# Arduino-DUE-SHEILD-4X4.net
KiCad netlist of a schematic drawn in EAGLE
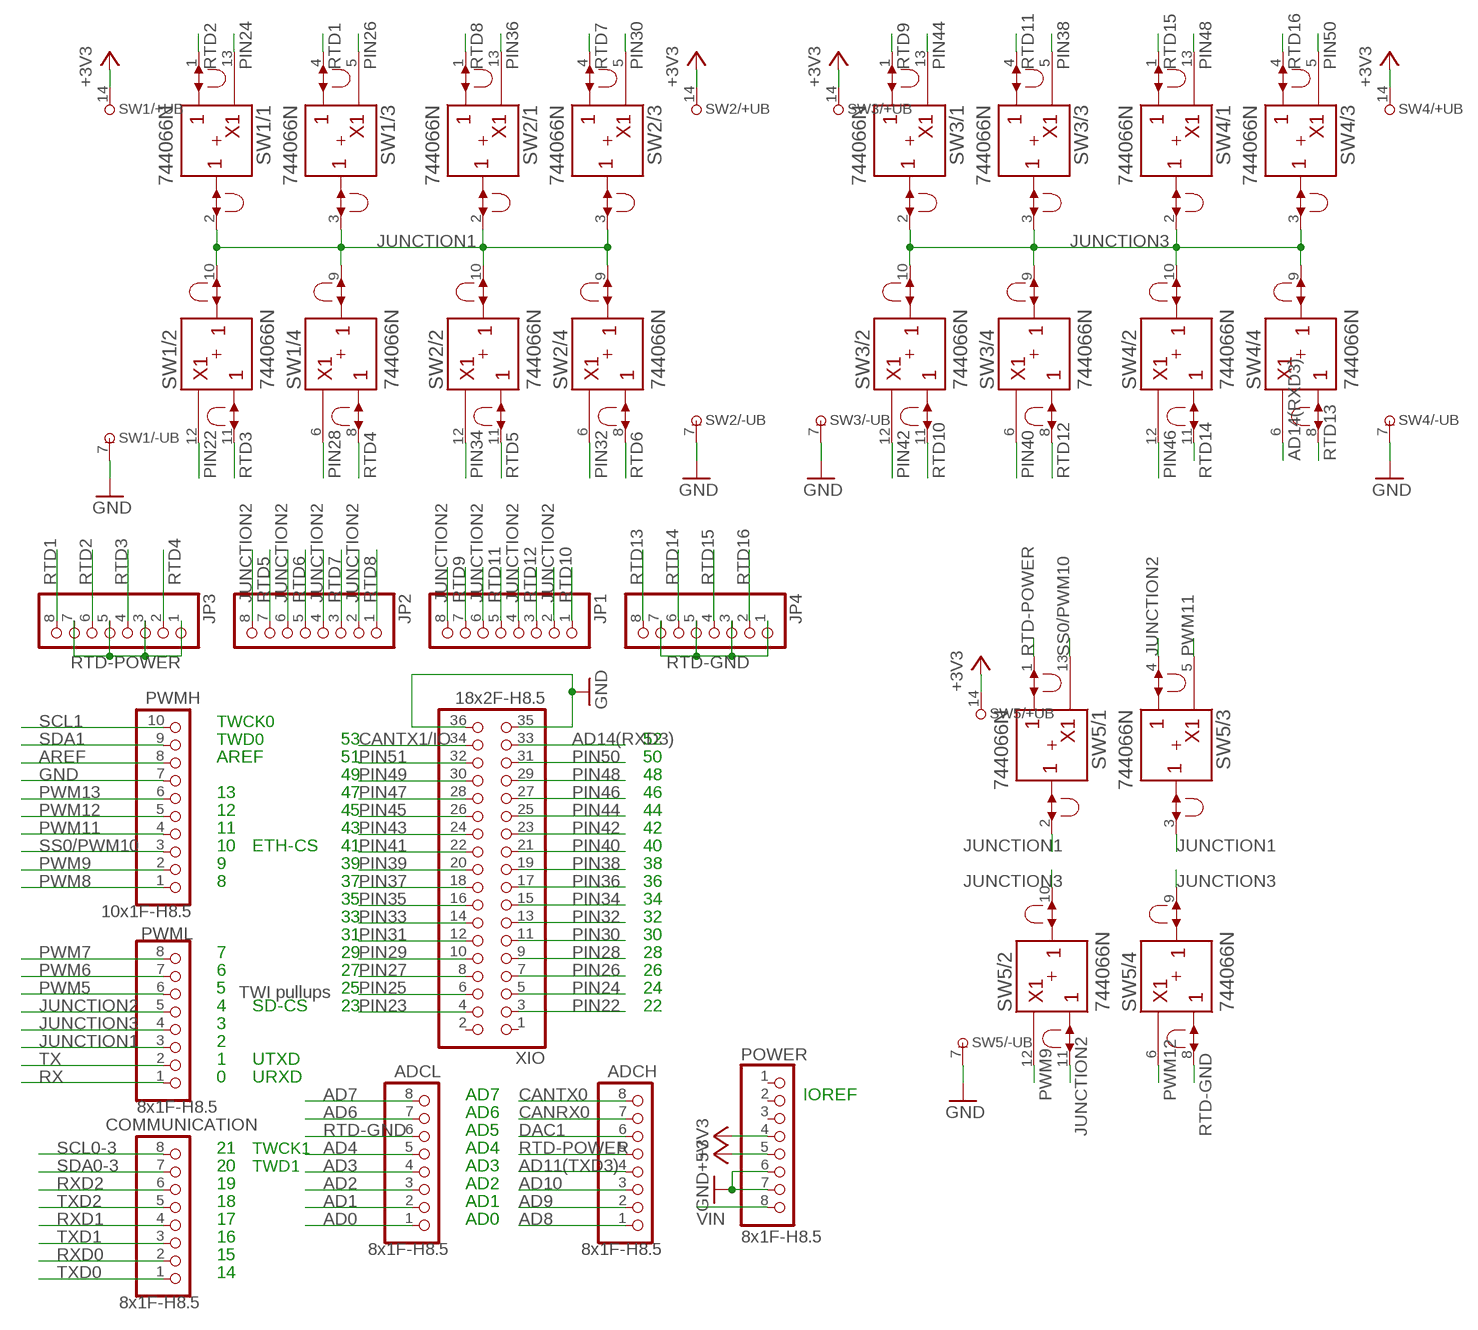
[diagram p0: schematic, sheet 1]

(export (version "E")
  (design (tool "Eeschema 10.0.6"))
  (components
    (comp (ref "ADCH")
      (value "8x1F-H8.5")
      (footprint "eagle-import:1X08")
      (libsource (lib "eagle-import") (part "PINHD-1X8"))
    )
    (comp (ref "ADCL")
      (value "8x1F-H8.5")
      (footprint "eagle-import:1X08")
      (libsource (lib "eagle-import") (part "PINHD-1X8"))
    )
    (comp (ref "COMMUNICATION")
      (value "8x1F-H8.5")
      (footprint "eagle-import:1X08")
      (libsource (lib "eagle-import") (part "PINHD-1X8"))
    )
    (comp (ref "JP1")
      (value "PINHD-1X8")
      (footprint "eagle-import:1X08")
      (libsource (lib "eagle-import") (part "pinhead_PINHD-1X8"))
    )
    (comp (ref "JP2")
      (value "PINHD-1X8")
      (footprint "eagle-import:1X08")
      (libsource (lib "eagle-import") (part "pinhead_PINHD-1X8"))
    )
    (comp (ref "JP3")
      (value "PINHD-1X8")
      (footprint "eagle-import:1X08")
      (libsource (lib "eagle-import") (part "pinhead_PINHD-1X8"))
    )
    (comp (ref "JP4")
      (value "PINHD-1X8")
      (footprint "eagle-import:1X08")
      (libsource (lib "eagle-import") (part "pinhead_PINHD-1X8"))
    )
    (comp (ref "POWER")
      (value "8x1F-H8.5")
      (footprint "eagle-import:1X08")
      (libsource (lib "eagle-import") (part "PINHD-1X8"))
    )
    (comp (ref "PWMH")
      (value "10x1F-H8.5")
      (footprint "eagle-import:1X10")
      (libsource (lib "eagle-import") (part "PINHD-1X10"))
    )
    (comp (ref "PWML")
      (value "8x1F-H8.5")
      (footprint "eagle-import:1X08")
      (libsource (lib "eagle-import") (part "PINHD-1X8"))
    )
    (comp (ref "SW1")
      (value "744066N")
      (footprint "eagle-import:DIL14")
      (libsource (lib "eagle-import") (part "744066N"))
    )
    (comp (ref "SW2")
      (value "744066N")
      (footprint "eagle-import:DIL14")
      (libsource (lib "eagle-import") (part "744066N"))
    )
    (comp (ref "SW3")
      (value "744066N")
      (footprint "eagle-import:DIL14")
      (libsource (lib "eagle-import") (part "744066N"))
    )
    (comp (ref "SW4")
      (value "744066N")
      (footprint "eagle-import:DIL14")
      (libsource (lib "eagle-import") (part "744066N"))
    )
    (comp (ref "SW5")
      (value "744066N")
      (footprint "eagle-import:DIL14")
      (libsource (lib "eagle-import") (part "744066N"))
    )
    (comp (ref "XIO")
      (value "18x2F-H8.5")
      (footprint "eagle-import:2X18")
      (libsource (lib "eagle-import") (part "PINHD-2X18"))
    )
  )
  (nets
    (net (code "1") (name "+3V3") (class "Default")
      (node (ref "POWER") (pin "4") (pinfunction "4_4") (pintype "passive"))
      (node (ref "SW1") (pin "14") (pinfunction "+UB_14") (pintype "power_in"))
      (node (ref "SW2") (pin "14") (pinfunction "+UB_14") (pintype "power_in"))
      (node (ref "SW3") (pin "14") (pinfunction "+UB_14") (pintype "power_in"))
      (node (ref "SW4") (pin "14") (pinfunction "+UB_14") (pintype "power_in"))
      (node (ref "SW5") (pin "14") (pinfunction "+UB_14") (pintype "power_in"))
    )
    (net (code "2") (name "+5V") (class "Default")
      (node (ref "POWER") (pin "5") (pinfunction "5_5") (pintype "passive"))
    )
    (net (code "3") (name "/AD0") (class "Default")
      (node (ref "ADCL") (pin "1") (pinfunction "1_1") (pintype "passive"))
    )
    (net (code "4") (name "/AD1") (class "Default")
      (node (ref "ADCL") (pin "2") (pinfunction "2_2") (pintype "passive"))
    )
    (net (code "5") (name "/AD2") (class "Default")
      (node (ref "ADCL") (pin "3") (pinfunction "3_3") (pintype "passive"))
    )
    (net (code "6") (name "/AD3") (class "Default")
      (node (ref "ADCL") (pin "4") (pinfunction "4_4") (pintype "passive"))
    )
    (net (code "7") (name "/AD4") (class "Default")
      (node (ref "ADCL") (pin "5") (pinfunction "5_5") (pintype "passive"))
    )
    (net (code "8") (name "/AD6") (class "Default")
      (node (ref "ADCL") (pin "7") (pinfunction "7_7") (pintype "passive"))
    )
    (net (code "9") (name "/AD7") (class "Default")
      (node (ref "ADCL") (pin "8") (pinfunction "8_8") (pintype "passive"))
    )
    (net (code "10") (name "/AD8") (class "Default")
      (node (ref "ADCH") (pin "1") (pinfunction "1_1") (pintype "passive"))
    )
    (net (code "11") (name "/AD9") (class "Default")
      (node (ref "ADCH") (pin "2") (pinfunction "2_2") (pintype "passive"))
    )
    (net (code "12") (name "/AD10") (class "Default")
      (node (ref "ADCH") (pin "3") (pinfunction "3_3") (pintype "passive"))
    )
    (net (code "13") (name "/AD11(TXD3)") (class "Default")
      (node (ref "ADCH") (pin "4") (pinfunction "4_4") (pintype "passive"))
    )
    (net (code "14") (name "/AD14(RXD3)") (class "Default")
      (node (ref "SW4") (pin "6") (pinfunction "C_6") (pintype "input"))
      (node (ref "XIO") (pin "33") (pinfunction "33_33") (pintype "passive"))
    )
    (net (code "15") (name "/AREF") (class "Default")
      (node (ref "PWMH") (pin "8") (pinfunction "8_8") (pintype "passive"))
    )
    (net (code "16") (name "/CANRX0") (class "Default")
      (node (ref "ADCH") (pin "7") (pinfunction "7_7") (pintype "passive"))
    )
    (net (code "17") (name "/CANTX0") (class "Default")
      (node (ref "ADCH") (pin "8") (pinfunction "8_8") (pintype "passive"))
    )
    (net (code "18") (name "/CANTX1{slash}IO") (class "Default")
      (node (ref "XIO") (pin "34") (pinfunction "34_34") (pintype "passive"))
    )
    (net (code "19") (name "/DAC1") (class "Default")
      (node (ref "ADCH") (pin "6") (pinfunction "6_6") (pintype "passive"))
    )
    (net (code "20") (name "/JUNCTION1") (class "Default")
      (node (ref "PWML") (pin "3") (pinfunction "3_3") (pintype "passive"))
      (node (ref "SW1") (pin "10") (pinfunction "B_10") (pintype "passive"))
      (node (ref "SW1") (pin "2") (pinfunction "B_2") (pintype "passive"))
      (node (ref "SW1") (pin "3") (pinfunction "B_3") (pintype "passive"))
      (node (ref "SW1") (pin "9") (pinfunction "B_9") (pintype "passive"))
      (node (ref "SW2") (pin "10") (pinfunction "B_10") (pintype "passive"))
      (node (ref "SW2") (pin "2") (pinfunction "B_2") (pintype "passive"))
      (node (ref "SW2") (pin "3") (pinfunction "B_3") (pintype "passive"))
      (node (ref "SW2") (pin "9") (pinfunction "B_9") (pintype "passive"))
      (node (ref "SW5") (pin "2") (pinfunction "B_2") (pintype "passive"))
      (node (ref "SW5") (pin "3") (pinfunction "B_3") (pintype "passive"))
    )
    (net (code "21") (name "/JUNCTION2") (class "Default")
      (node (ref "JP1") (pin "2") (pinfunction "2_2") (pintype "passive"))
      (node (ref "JP1") (pin "4") (pinfunction "4_4") (pintype "passive"))
      (node (ref "JP1") (pin "6") (pinfunction "6_6") (pintype "passive"))
      (node (ref "JP1") (pin "8") (pinfunction "8_8") (pintype "passive"))
      (node (ref "JP2") (pin "2") (pinfunction "2_2") (pintype "passive"))
      (node (ref "JP2") (pin "4") (pinfunction "4_4") (pintype "passive"))
      (node (ref "JP2") (pin "6") (pinfunction "6_6") (pintype "passive"))
      (node (ref "JP2") (pin "8") (pinfunction "8_8") (pintype "passive"))
      (node (ref "PWML") (pin "5") (pinfunction "5_5") (pintype "passive"))
      (node (ref "SW5") (pin "11") (pinfunction "A_11") (pintype "passive"))
      (node (ref "SW5") (pin "4") (pinfunction "A_4") (pintype "passive"))
    )
    (net (code "22") (name "/JUNCTION3") (class "Default")
      (node (ref "PWML") (pin "4") (pinfunction "4_4") (pintype "passive"))
      (node (ref "SW3") (pin "10") (pinfunction "B_10") (pintype "passive"))
      (node (ref "SW3") (pin "2") (pinfunction "B_2") (pintype "passive"))
      (node (ref "SW3") (pin "3") (pinfunction "B_3") (pintype "passive"))
      (node (ref "SW3") (pin "9") (pinfunction "B_9") (pintype "passive"))
      (node (ref "SW4") (pin "10") (pinfunction "B_10") (pintype "passive"))
      (node (ref "SW4") (pin "2") (pinfunction "B_2") (pintype "passive"))
      (node (ref "SW4") (pin "3") (pinfunction "B_3") (pintype "passive"))
      (node (ref "SW4") (pin "9") (pinfunction "B_9") (pintype "passive"))
      (node (ref "SW5") (pin "10") (pinfunction "B_10") (pintype "passive"))
      (node (ref "SW5") (pin "9") (pinfunction "B_9") (pintype "passive"))
    )
    (net (code "23") (name "/PIN22") (class "Default")
      (node (ref "SW1") (pin "12") (pinfunction "C_12") (pintype "input"))
      (node (ref "XIO") (pin "3") (pinfunction "3_3") (pintype "passive"))
    )
    (net (code "24") (name "/PIN23") (class "Default")
      (node (ref "XIO") (pin "4") (pinfunction "4_4") (pintype "passive"))
    )
    (net (code "25") (name "/PIN24") (class "Default")
      (node (ref "SW1") (pin "13") (pinfunction "C_13") (pintype "input"))
      (node (ref "XIO") (pin "5") (pinfunction "5_5") (pintype "passive"))
    )
    (net (code "26") (name "/PIN25") (class "Default")
      (node (ref "XIO") (pin "6") (pinfunction "6_6") (pintype "passive"))
    )
    (net (code "27") (name "/PIN26") (class "Default")
      (node (ref "SW1") (pin "5") (pinfunction "C_5") (pintype "input"))
      (node (ref "XIO") (pin "7") (pinfunction "7_7") (pintype "passive"))
    )
    (net (code "28") (name "/PIN27") (class "Default")
      (node (ref "XIO") (pin "8") (pinfunction "8_8") (pintype "passive"))
    )
    (net (code "29") (name "/PIN28") (class "Default")
      (node (ref "SW1") (pin "6") (pinfunction "C_6") (pintype "input"))
      (node (ref "XIO") (pin "9") (pinfunction "9_9") (pintype "passive"))
    )
    (net (code "30") (name "/PIN29") (class "Default")
      (node (ref "XIO") (pin "10") (pinfunction "10_10") (pintype "passive"))
    )
    (net (code "31") (name "/PIN30") (class "Default")
      (node (ref "SW2") (pin "5") (pinfunction "C_5") (pintype "input"))
      (node (ref "XIO") (pin "11") (pinfunction "11_11") (pintype "passive"))
    )
    (net (code "32") (name "/PIN31") (class "Default")
      (node (ref "XIO") (pin "12") (pinfunction "12_12") (pintype "passive"))
    )
    (net (code "33") (name "/PIN32") (class "Default")
      (node (ref "SW2") (pin "6") (pinfunction "C_6") (pintype "input"))
      (node (ref "XIO") (pin "13") (pinfunction "13_13") (pintype "passive"))
    )
    (net (code "34") (name "/PIN33") (class "Default")
      (node (ref "XIO") (pin "14") (pinfunction "14_14") (pintype "passive"))
    )
    (net (code "35") (name "/PIN34") (class "Default")
      (node (ref "SW2") (pin "12") (pinfunction "C_12") (pintype "input"))
      (node (ref "XIO") (pin "15") (pinfunction "15_15") (pintype "passive"))
    )
    (net (code "36") (name "/PIN35") (class "Default")
      (node (ref "XIO") (pin "16") (pinfunction "16_16") (pintype "passive"))
    )
    (net (code "37") (name "/PIN36") (class "Default")
      (node (ref "SW2") (pin "13") (pinfunction "C_13") (pintype "input"))
      (node (ref "XIO") (pin "17") (pinfunction "17_17") (pintype "passive"))
    )
    (net (code "38") (name "/PIN37") (class "Default")
      (node (ref "XIO") (pin "18") (pinfunction "18_18") (pintype "passive"))
    )
    (net (code "39") (name "/PIN38") (class "Default")
      (node (ref "SW3") (pin "5") (pinfunction "C_5") (pintype "input"))
      (node (ref "XIO") (pin "19") (pinfunction "19_19") (pintype "passive"))
    )
    (net (code "40") (name "/PIN39") (class "Default")
      (node (ref "XIO") (pin "20") (pinfunction "20_20") (pintype "passive"))
    )
    (net (code "41") (name "/PIN40") (class "Default")
      (node (ref "SW3") (pin "6") (pinfunction "C_6") (pintype "input"))
      (node (ref "XIO") (pin "21") (pinfunction "21_21") (pintype "passive"))
    )
    (net (code "42") (name "/PIN41") (class "Default")
      (node (ref "XIO") (pin "22") (pinfunction "22_22") (pintype "passive"))
    )
    (net (code "43") (name "/PIN42") (class "Default")
      (node (ref "SW3") (pin "12") (pinfunction "C_12") (pintype "input"))
      (node (ref "XIO") (pin "23") (pinfunction "23_23") (pintype "passive"))
    )
    (net (code "44") (name "/PIN43") (class "Default")
      (node (ref "XIO") (pin "24") (pinfunction "24_24") (pintype "passive"))
    )
    (net (code "45") (name "/PIN44") (class "Default")
      (node (ref "SW3") (pin "13") (pinfunction "C_13") (pintype "input"))
      (node (ref "XIO") (pin "25") (pinfunction "25_25") (pintype "passive"))
    )
    (net (code "46") (name "/PIN45") (class "Default")
      (node (ref "XIO") (pin "26") (pinfunction "26_26") (pintype "passive"))
    )
    (net (code "47") (name "/PIN46") (class "Default")
      (node (ref "SW4") (pin "12") (pinfunction "C_12") (pintype "input"))
      (node (ref "XIO") (pin "27") (pinfunction "27_27") (pintype "passive"))
    )
    (net (code "48") (name "/PIN47") (class "Default")
      (node (ref "XIO") (pin "28") (pinfunction "28_28") (pintype "passive"))
    )
    (net (code "49") (name "/PIN48") (class "Default")
      (node (ref "SW4") (pin "13") (pinfunction "C_13") (pintype "input"))
      (node (ref "XIO") (pin "29") (pinfunction "29_29") (pintype "passive"))
    )
    (net (code "50") (name "/PIN49") (class "Default")
      (node (ref "XIO") (pin "30") (pinfunction "30_30") (pintype "passive"))
    )
    (net (code "51") (name "/PIN50") (class "Default")
      (node (ref "SW4") (pin "5") (pinfunction "C_5") (pintype "input"))
      (node (ref "XIO") (pin "31") (pinfunction "31_31") (pintype "passive"))
    )
    (net (code "52") (name "/PIN51") (class "Default")
      (node (ref "XIO") (pin "32") (pinfunction "32_32") (pintype "passive"))
    )
    (net (code "53") (name "/PWM5") (class "Default")
      (node (ref "PWML") (pin "6") (pinfunction "6_6") (pintype "passive"))
    )
    (net (code "54") (name "/PWM6") (class "Default")
      (node (ref "PWML") (pin "7") (pinfunction "7_7") (pintype "passive"))
    )
    (net (code "55") (name "/PWM7") (class "Default")
      (node (ref "PWML") (pin "8") (pinfunction "8_8") (pintype "passive"))
    )
    (net (code "56") (name "/PWM8") (class "Default")
      (node (ref "PWMH") (pin "1") (pinfunction "1_1") (pintype "passive"))
    )
    (net (code "57") (name "/PWM9") (class "Default")
      (node (ref "PWMH") (pin "2") (pinfunction "2_2") (pintype "passive"))
      (node (ref "SW5") (pin "12") (pinfunction "C_12") (pintype "input"))
    )
    (net (code "58") (name "/PWM11") (class "Default")
      (node (ref "PWMH") (pin "4") (pinfunction "4_4") (pintype "passive"))
      (node (ref "SW5") (pin "5") (pinfunction "C_5") (pintype "input"))
    )
    (net (code "59") (name "/PWM12") (class "Default")
      (node (ref "PWMH") (pin "5") (pinfunction "5_5") (pintype "passive"))
      (node (ref "SW5") (pin "6") (pinfunction "C_6") (pintype "input"))
    )
    (net (code "60") (name "/PWM13") (class "Default")
      (node (ref "PWMH") (pin "6") (pinfunction "6_6") (pintype "passive"))
    )
    (net (code "61") (name "/RTD-GND") (class "Default")
      (node (ref "ADCL") (pin "6") (pinfunction "6_6") (pintype "passive"))
      (node (ref "JP4") (pin "1") (pinfunction "1_1") (pintype "passive"))
      (node (ref "JP4") (pin "3") (pinfunction "3_3") (pintype "passive"))
      (node (ref "JP4") (pin "5") (pinfunction "5_5") (pintype "passive"))
      (node (ref "JP4") (pin "7") (pinfunction "7_7") (pintype "passive"))
      (node (ref "SW5") (pin "8") (pinfunction "A_8") (pintype "passive"))
    )
    (net (code "62") (name "/RTD-POWER") (class "Default")
      (node (ref "ADCH") (pin "5") (pinfunction "5_5") (pintype "passive"))
      (node (ref "JP3") (pin "1") (pinfunction "1_1") (pintype "passive"))
      (node (ref "JP3") (pin "3") (pinfunction "3_3") (pintype "passive"))
      (node (ref "JP3") (pin "5") (pinfunction "5_5") (pintype "passive"))
      (node (ref "JP3") (pin "7") (pinfunction "7_7") (pintype "passive"))
      (node (ref "SW5") (pin "1") (pinfunction "A_1") (pintype "passive"))
    )
    (net (code "63") (name "/RTD1") (class "Default")
      (node (ref "JP3") (pin "8") (pinfunction "8_8") (pintype "passive"))
      (node (ref "SW1") (pin "4") (pinfunction "A_4") (pintype "passive"))
    )
    (net (code "64") (name "/RTD2") (class "Default")
      (node (ref "JP3") (pin "6") (pinfunction "6_6") (pintype "passive"))
      (node (ref "SW1") (pin "1") (pinfunction "A_1") (pintype "passive"))
    )
    (net (code "65") (name "/RTD3") (class "Default")
      (node (ref "JP3") (pin "4") (pinfunction "4_4") (pintype "passive"))
      (node (ref "SW1") (pin "11") (pinfunction "A_11") (pintype "passive"))
    )
    (net (code "66") (name "/RTD4") (class "Default")
      (node (ref "JP3") (pin "2") (pinfunction "2_2") (pintype "passive"))
      (node (ref "SW1") (pin "8") (pinfunction "A_8") (pintype "passive"))
    )
    (net (code "67") (name "/RTD5") (class "Default")
      (node (ref "JP2") (pin "7") (pinfunction "7_7") (pintype "passive"))
      (node (ref "SW2") (pin "11") (pinfunction "A_11") (pintype "passive"))
    )
    (net (code "68") (name "/RTD6") (class "Default")
      (node (ref "JP2") (pin "5") (pinfunction "5_5") (pintype "passive"))
      (node (ref "SW2") (pin "8") (pinfunction "A_8") (pintype "passive"))
    )
    (net (code "69") (name "/RTD7") (class "Default")
      (node (ref "JP2") (pin "3") (pinfunction "3_3") (pintype "passive"))
      (node (ref "SW2") (pin "4") (pinfunction "A_4") (pintype "passive"))
    )
    (net (code "70") (name "/RTD8") (class "Default")
      (node (ref "JP2") (pin "1") (pinfunction "1_1") (pintype "passive"))
      (node (ref "SW2") (pin "1") (pinfunction "A_1") (pintype "passive"))
    )
    (net (code "71") (name "/RTD9") (class "Default")
      (node (ref "JP1") (pin "7") (pinfunction "7_7") (pintype "passive"))
      (node (ref "SW3") (pin "1") (pinfunction "A_1") (pintype "passive"))
    )
    (net (code "72") (name "/RTD10") (class "Default")
      (node (ref "JP1") (pin "1") (pinfunction "1_1") (pintype "passive"))
      (node (ref "SW3") (pin "11") (pinfunction "A_11") (pintype "passive"))
    )
    (net (code "73") (name "/RTD11") (class "Default")
      (node (ref "JP1") (pin "5") (pinfunction "5_5") (pintype "passive"))
      (node (ref "SW3") (pin "4") (pinfunction "A_4") (pintype "passive"))
    )
    (net (code "74") (name "/RTD12") (class "Default")
      (node (ref "JP1") (pin "3") (pinfunction "3_3") (pintype "passive"))
      (node (ref "SW3") (pin "8") (pinfunction "A_8") (pintype "passive"))
    )
    (net (code "75") (name "/RTD13") (class "Default")
      (node (ref "JP4") (pin "8") (pinfunction "8_8") (pintype "passive"))
      (node (ref "SW4") (pin "8") (pinfunction "A_8") (pintype "passive"))
    )
    (net (code "76") (name "/RTD14") (class "Default")
      (node (ref "JP4") (pin "6") (pinfunction "6_6") (pintype "passive"))
      (node (ref "SW4") (pin "11") (pinfunction "A_11") (pintype "passive"))
    )
    (net (code "77") (name "/RTD15") (class "Default")
      (node (ref "JP4") (pin "4") (pinfunction "4_4") (pintype "passive"))
      (node (ref "SW4") (pin "1") (pinfunction "A_1") (pintype "passive"))
    )
    (net (code "78") (name "/RTD16") (class "Default")
      (node (ref "JP4") (pin "2") (pinfunction "2_2") (pintype "passive"))
      (node (ref "SW4") (pin "4") (pinfunction "A_4") (pintype "passive"))
    )
    (net (code "79") (name "/RX") (class "Default")
      (node (ref "PWML") (pin "1") (pinfunction "1_1") (pintype "passive"))
    )
    (net (code "80") (name "/RXD0") (class "Default")
      (node (ref "COMMUNICATION") (pin "2") (pinfunction "2_2") (pintype "passive"))
    )
    (net (code "81") (name "/RXD1") (class "Default")
      (node (ref "COMMUNICATION") (pin "4") (pinfunction "4_4") (pintype "passive"))
    )
    (net (code "82") (name "/RXD2") (class "Default")
      (node (ref "COMMUNICATION") (pin "6") (pinfunction "6_6") (pintype "passive"))
    )
    (net (code "83") (name "/SCL0-3") (class "Default")
      (node (ref "COMMUNICATION") (pin "8") (pinfunction "8_8") (pintype "passive"))
    )
    (net (code "84") (name "/SCL1") (class "Default")
      (node (ref "PWMH") (pin "10") (pinfunction "10_10") (pintype "passive"))
    )
    (net (code "85") (name "/SDA0-3") (class "Default")
      (node (ref "COMMUNICATION") (pin "7") (pinfunction "7_7") (pintype "passive"))
    )
    (net (code "86") (name "/SDA1") (class "Default")
      (node (ref "PWMH") (pin "9") (pinfunction "9_9") (pintype "passive"))
    )
    (net (code "87") (name "/SS0{slash}PWM10") (class "Default")
      (node (ref "PWMH") (pin "3") (pinfunction "3_3") (pintype "passive"))
      (node (ref "SW5") (pin "13") (pinfunction "C_13") (pintype "input"))
    )
    (net (code "88") (name "/TX") (class "Default")
      (node (ref "PWML") (pin "2") (pinfunction "2_2") (pintype "passive"))
    )
    (net (code "89") (name "/TXD0") (class "Default")
      (node (ref "COMMUNICATION") (pin "1") (pinfunction "1_1") (pintype "passive"))
    )
    (net (code "90") (name "/TXD1") (class "Default")
      (node (ref "COMMUNICATION") (pin "3") (pinfunction "3_3") (pintype "passive"))
    )
    (net (code "91") (name "/TXD2") (class "Default")
      (node (ref "COMMUNICATION") (pin "5") (pinfunction "5_5") (pintype "passive"))
    )
    (net (code "92") (name "/VIN") (class "Default")
      (node (ref "POWER") (pin "8") (pinfunction "8_8") (pintype "passive"))
    )
    (net (code "93") (name "GND") (class "Default")
      (node (ref "POWER") (pin "6") (pinfunction "6_6") (pintype "passive"))
      (node (ref "POWER") (pin "7") (pinfunction "7_7") (pintype "passive"))
      (node (ref "PWMH") (pin "7") (pinfunction "7_7") (pintype "passive"))
      (node (ref "SW1") (pin "7") (pinfunction "-UB_7") (pintype "power_in"))
      (node (ref "SW2") (pin "7") (pinfunction "-UB_7") (pintype "power_in"))
      (node (ref "SW3") (pin "7") (pinfunction "-UB_7") (pintype "power_in"))
      (node (ref "SW4") (pin "7") (pinfunction "-UB_7") (pintype "power_in"))
      (node (ref "SW5") (pin "7") (pinfunction "-UB_7") (pintype "power_in"))
      (node (ref "XIO") (pin "35") (pinfunction "35_35") (pintype "passive"))
      (node (ref "XIO") (pin "36") (pinfunction "36_36") (pintype "passive"))
    )
    (net (code "94") (name "unconnected-(POWER-Pad1)") (class "Default")
      (node (ref "POWER") (pin "1") (pinfunction "1_1") (pintype "passive"))
    )
    (net (code "95") (name "unconnected-(POWER-Pad2)") (class "Default")
      (node (ref "POWER") (pin "2") (pinfunction "2_2") (pintype "passive"))
    )
    (net (code "96") (name "unconnected-(POWER-Pad3)") (class "Default")
      (node (ref "POWER") (pin "3") (pinfunction "3_3") (pintype "passive"))
    )
    (net (code "97") (name "unconnected-(XIO-Pad1)") (class "Default")
      (node (ref "XIO") (pin "1") (pinfunction "1_1") (pintype "passive"))
    )
    (net (code "98") (name "unconnected-(XIO-Pad2)") (class "Default")
      (node (ref "XIO") (pin "2") (pinfunction "2_2") (pintype "passive"))
    )
  )
)
